# CNC-MainBoard.net
KiCad netlist of a schematic drawn in EAGLE
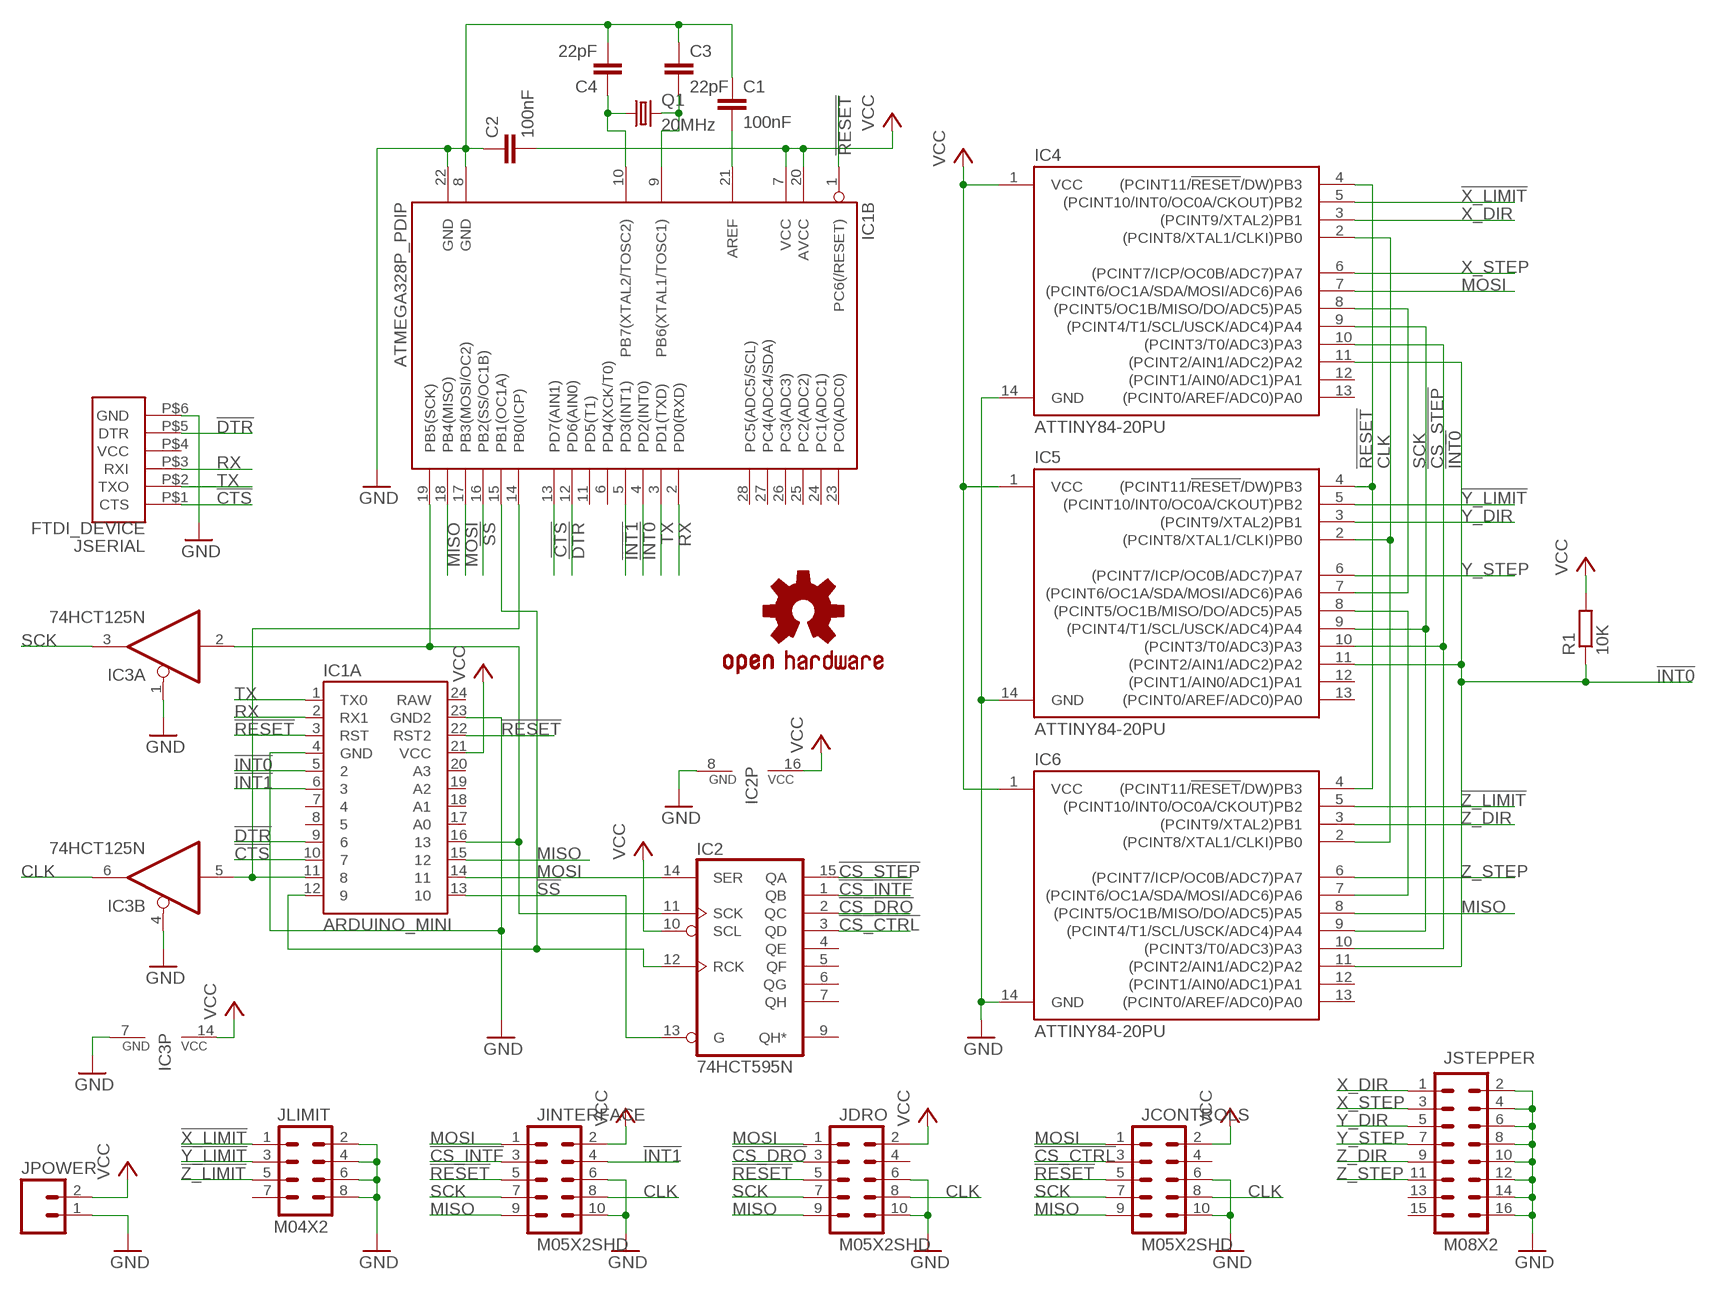
[diagram p0: schematic, sheet 1]

(export (version "E")
  (design (tool "Eeschema 10.0.6"))
  (components
    (comp (ref "C1")
      (value "100nF")
      (footprint "eagle-import:C050-025X075")
      (libsource (lib "eagle-import") (part "C-EU050-025X075"))
    )
    (comp (ref "C2")
      (value "100nF")
      (footprint "eagle-import:C050-025X075")
      (libsource (lib "eagle-import") (part "C-EU050-025X075"))
    )
    (comp (ref "C3")
      (value "22pF")
      (footprint "eagle-import:C050-025X075")
      (libsource (lib "eagle-import") (part "C-EU050-025X075"))
    )
    (comp (ref "C4")
      (value "22pF")
      (footprint "eagle-import:C050-025X075")
      (libsource (lib "eagle-import") (part "C-EU050-025X075"))
    )
    (comp (ref "IC1A")
      (value "ARDUINO_MINI")
      (footprint "eagle-import:ARDUINO_MINI")
      (libsource (lib "eagle-import") (part "ARDUINO_MINI"))
    )
    (comp (ref "IC1B")
      (value "ATMEGA328P_PDIP")
      (footprint "eagle-import:DIL28-3")
      (libsource (lib "eagle-import") (part "ATMEGA328P_PDIP"))
    )
    (comp (ref "IC2")
      (value "74HCT595N")
      (footprint "eagle-import:DIL16")
      (libsource (lib "eagle-import") (part "74595NHCT"))
    )
    (comp (ref "IC3")
      (value "74HCT125N")
      (footprint "eagle-import:DIL14")
      (libsource (lib "eagle-import") (part "74125NHCT"))
    )
    (comp (ref "IC4")
      (value "ATTINY84-20PU")
      (footprint "eagle-import:DIL14")
      (libsource (lib "eagle-import") (part "ATTINY84PU-20"))
    )
    (comp (ref "IC5")
      (value "ATTINY84-20PU")
      (footprint "eagle-import:DIL14")
      (libsource (lib "eagle-import") (part "ATTINY84PU-20"))
    )
    (comp (ref "IC6")
      (value "ATTINY84-20PU")
      (footprint "eagle-import:DIL14")
      (libsource (lib "eagle-import") (part "ATTINY84PU-20"))
    )
    (comp (ref "JCONTROLS")
      (value "M05X2SHD")
      (footprint "eagle-import:2X5-SHROUDED")
      (libsource (lib "eagle-import") (part "M05X2SHD"))
    )
    (comp (ref "JDRO")
      (value "M05X2SHD")
      (footprint "eagle-import:2X5-SHROUDED")
      (libsource (lib "eagle-import") (part "M05X2SHD"))
    )
    (comp (ref "JINTERFACE")
      (value "M05X2SHD")
      (footprint "eagle-import:2X5-SHROUDED")
      (libsource (lib "eagle-import") (part "M05X2SHD"))
    )
    (comp (ref "JLIMIT")
      (value "M04X2")
      (footprint "eagle-import:2X4")
      (libsource (lib "eagle-import") (part "M04X2"))
    )
    (comp (ref "JPOWER")
      (value "M02POLAR")
      (footprint "eagle-import:MOLEX-1X2")
      (libsource (lib "eagle-import") (part "M02POLAR"))
    )
    (comp (ref "JSERIAL")
      (value "FTDI_DEVICE")
      (footprint "eagle-import:FTDI_DEVICE_SIDE")
      (libsource (lib "eagle-import") (part "FTDI_DEVICE"))
    )
    (comp (ref "JSTEPPER")
      (value "M08X2")
      (footprint "eagle-import:2X8")
      (libsource (lib "eagle-import") (part "M08X2"))
    )
    (comp (ref "Q1")
      (value "20MHz")
      (footprint "eagle-import:HC49U-V")
      (libsource (lib "eagle-import") (part "CRYSTALHC49U-V"))
    )
    (comp (ref "R1")
      (value "10K")
      (footprint "eagle-import:0207_10")
      (libsource (lib "eagle-import") (part "R-EU_0207/10"))
    )
    (comp (ref "U$1")
      (value "SPARKFUN_OSHW-LOGOL")
      (footprint "eagle-import:SPARKFUN_OSHW-LOGO-L")
      (libsource (lib "eagle-import") (part "SPARKFUN_OSHW-LOGOL"))
    )
  )
  (nets
    (net (code "1") (name "/CLK") (class "Default")
      (node (ref "IC3") (pin "6") (pinfunction "O_6") (pintype "tri_state"))
      (node (ref "IC4") (pin "2") (pinfunction "(PCINT8/XTAL1/CLKI)PB0_2") (pintype "bidirectional"))
      (node (ref "IC5") (pin "2") (pinfunction "(PCINT8/XTAL1/CLKI)PB0_2") (pintype "bidirectional"))
      (node (ref "IC6") (pin "2") (pinfunction "(PCINT8/XTAL1/CLKI)PB0_2") (pintype "bidirectional"))
      (node (ref "JCONTROLS") (pin "8") (pinfunction "8_8") (pintype "passive"))
      (node (ref "JDRO") (pin "8") (pinfunction "8_8") (pintype "passive"))
      (node (ref "JINTERFACE") (pin "8") (pinfunction "8_8") (pintype "passive"))
    )
    (net (code "2") (name "/MISO") (class "Default")
      (node (ref "IC1A") (pin "15") (pinfunction "12_15") (pintype "bidirectional"))
      (node (ref "IC1B") (pin "18") (pinfunction "PB4(MISO)_18") (pintype "bidirectional"))
      (node (ref "IC6") (pin "8") (pinfunction "(PCINT5/OC1B/MISO/DO/ADC5)PA5_8") (pintype "bidirectional"))
      (node (ref "JCONTROLS") (pin "9") (pinfunction "9_9") (pintype "passive"))
      (node (ref "JDRO") (pin "9") (pinfunction "9_9") (pintype "passive"))
      (node (ref "JINTERFACE") (pin "9") (pinfunction "9_9") (pintype "passive"))
    )
    (net (code "3") (name "/MOSI") (class "Default")
      (node (ref "IC1A") (pin "14") (pinfunction "11_14") (pintype "bidirectional"))
      (node (ref "IC1B") (pin "17") (pinfunction "PB3(MOSI/OC2)_17") (pintype "bidirectional"))
      (node (ref "IC2") (pin "14") (pinfunction "SER_14") (pintype "input"))
      (node (ref "IC4") (pin "7") (pinfunction "(PCINT6/OC1A/SDA/MOSI/ADC6)PA6_7") (pintype "bidirectional"))
      (node (ref "JCONTROLS") (pin "1") (pinfunction "1_1") (pintype "passive"))
      (node (ref "JDRO") (pin "1") (pinfunction "1_1") (pintype "passive"))
      (node (ref "JINTERFACE") (pin "1") (pinfunction "1_1") (pintype "passive"))
    )
    (net (code "4") (name "/RX") (class "Default")
      (node (ref "IC1A") (pin "2") (pinfunction "RX1_2") (pintype "bidirectional"))
      (node (ref "IC1B") (pin "2") (pinfunction "PD0(RXD)_2") (pintype "bidirectional"))
      (node (ref "JSERIAL") (pin "P$3") (pinfunction "RXI_P$3") (pintype "bidirectional"))
    )
    (net (code "5") (name "/SCK") (class "Default")
      (node (ref "IC3") (pin "3") (pinfunction "O_3") (pintype "tri_state"))
      (node (ref "IC4") (pin "9") (pinfunction "(PCINT4/T1/SCL/USCK/ADC4)PA4_9") (pintype "bidirectional"))
      (node (ref "IC5") (pin "9") (pinfunction "(PCINT4/T1/SCL/USCK/ADC4)PA4_9") (pintype "bidirectional"))
      (node (ref "IC6") (pin "9") (pinfunction "(PCINT4/T1/SCL/USCK/ADC4)PA4_9") (pintype "bidirectional"))
      (node (ref "JCONTROLS") (pin "7") (pinfunction "7_7") (pintype "passive"))
      (node (ref "JDRO") (pin "7") (pinfunction "7_7") (pintype "passive"))
      (node (ref "JINTERFACE") (pin "7") (pinfunction "7_7") (pintype "passive"))
    )
    (net (code "6") (name "/TX") (class "Default")
      (node (ref "IC1A") (pin "1") (pinfunction "TX0_1") (pintype "bidirectional"))
      (node (ref "IC1B") (pin "3") (pinfunction "PD1(TXD)_3") (pintype "bidirectional"))
      (node (ref "JSERIAL") (pin "P$2") (pinfunction "TXO_P$2") (pintype "bidirectional"))
    )
    (net (code "7") (name "/X_DIR") (class "Default")
      (node (ref "IC4") (pin "3") (pinfunction "(PCINT9/XTAL2)PB1_3") (pintype "bidirectional"))
      (node (ref "JSTEPPER") (pin "1") (pinfunction "1_1") (pintype "passive"))
    )
    (net (code "8") (name "/X_STEP") (class "Default")
      (node (ref "IC4") (pin "6") (pinfunction "(PCINT7/ICP/OC0B/ADC7)PA7_6") (pintype "bidirectional"))
      (node (ref "JSTEPPER") (pin "3") (pinfunction "3_3") (pintype "passive"))
    )
    (net (code "9") (name "/Y_DIR") (class "Default")
      (node (ref "IC5") (pin "3") (pinfunction "(PCINT9/XTAL2)PB1_3") (pintype "bidirectional"))
      (node (ref "JSTEPPER") (pin "5") (pinfunction "5_5") (pintype "passive"))
    )
    (net (code "10") (name "/Y_STEP") (class "Default")
      (node (ref "IC5") (pin "6") (pinfunction "(PCINT7/ICP/OC0B/ADC7)PA7_6") (pintype "bidirectional"))
      (node (ref "JSTEPPER") (pin "7") (pinfunction "7_7") (pintype "passive"))
    )
    (net (code "11") (name "/Z_DIR") (class "Default")
      (node (ref "IC6") (pin "3") (pinfunction "(PCINT9/XTAL2)PB1_3") (pintype "bidirectional"))
      (node (ref "JSTEPPER") (pin "9") (pinfunction "9_9") (pintype "passive"))
    )
    (net (code "12") (name "/Z_STEP") (class "Default")
      (node (ref "IC6") (pin "6") (pinfunction "(PCINT7/ICP/OC0B/ADC7)PA7_6") (pintype "bidirectional"))
      (node (ref "JSTEPPER") (pin "11") (pinfunction "11_11") (pintype "passive"))
    )
    (net (code "13") (name "/~{CS_CTRL}") (class "Default")
      (node (ref "IC2") (pin "3") (pinfunction "QD_3") (pintype "tri_state"))
      (node (ref "JCONTROLS") (pin "3") (pinfunction "3_3") (pintype "passive"))
    )
    (net (code "14") (name "/~{CS_DRO}") (class "Default")
      (node (ref "IC2") (pin "2") (pinfunction "QC_2") (pintype "tri_state"))
      (node (ref "JDRO") (pin "3") (pinfunction "3_3") (pintype "passive"))
    )
    (net (code "15") (name "/~{CS_INTF}") (class "Default")
      (node (ref "IC2") (pin "1") (pinfunction "QB_1") (pintype "tri_state"))
      (node (ref "JINTERFACE") (pin "3") (pinfunction "3_3") (pintype "passive"))
    )
    (net (code "16") (name "/~{CS_STEP}") (class "Default")
      (node (ref "IC2") (pin "15") (pinfunction "QA_15") (pintype "tri_state"))
      (node (ref "IC4") (pin "10") (pinfunction "(PCINT3/T0/ADC3)PA3_10") (pintype "bidirectional"))
      (node (ref "IC5") (pin "10") (pinfunction "(PCINT3/T0/ADC3)PA3_10") (pintype "bidirectional"))
      (node (ref "IC6") (pin "10") (pinfunction "(PCINT3/T0/ADC3)PA3_10") (pintype "bidirectional"))
    )
    (net (code "17") (name "/~{CTS}") (class "Default")
      (node (ref "IC1A") (pin "10") (pinfunction "7_10") (pintype "bidirectional"))
      (node (ref "IC1B") (pin "13") (pinfunction "PD7(AIN1)_13") (pintype "bidirectional"))
      (node (ref "JSERIAL") (pin "P$1") (pinfunction "CTS_P$1") (pintype "bidirectional"))
    )
    (net (code "18") (name "/~{DTR}") (class "Default")
      (node (ref "IC1A") (pin "9") (pinfunction "6_9") (pintype "bidirectional"))
      (node (ref "IC1B") (pin "12") (pinfunction "PD6(AIN0)_12") (pintype "bidirectional"))
      (node (ref "JSERIAL") (pin "P$5") (pinfunction "DTR_P$5") (pintype "bidirectional"))
    )
    (net (code "19") (name "/~{INT0}") (class "Default")
      (node (ref "IC1A") (pin "5") (pinfunction "2_5") (pintype "bidirectional"))
      (node (ref "IC1B") (pin "4") (pinfunction "PD2(INT0)_4") (pintype "bidirectional"))
      (node (ref "IC4") (pin "11") (pinfunction "(PCINT2/AIN1/ADC2)PA2_11") (pintype "bidirectional"))
      (node (ref "IC5") (pin "11") (pinfunction "(PCINT2/AIN1/ADC2)PA2_11") (pintype "bidirectional"))
      (node (ref "IC6") (pin "11") (pinfunction "(PCINT2/AIN1/ADC2)PA2_11") (pintype "bidirectional"))
      (node (ref "R1") (pin "1") (pinfunction "1_1") (pintype "passive"))
    )
    (net (code "20") (name "/~{INT1}") (class "Default")
      (node (ref "IC1A") (pin "6") (pinfunction "3_6") (pintype "bidirectional"))
      (node (ref "IC1B") (pin "5") (pinfunction "PD3(INT1)_5") (pintype "bidirectional"))
      (node (ref "JINTERFACE") (pin "4") (pinfunction "4_4") (pintype "passive"))
    )
    (net (code "21") (name "/~{RESET}") (class "Default")
      (node (ref "IC1A") (pin "22") (pinfunction "RST2_22") (pintype "bidirectional"))
      (node (ref "IC1A") (pin "3") (pinfunction "RST_3") (pintype "bidirectional"))
      (node (ref "IC1B") (pin "1") (pinfunction "PC6(/RESET)_1") (pintype "bidirectional"))
      (node (ref "IC4") (pin "4") (pinfunction "(PCINT11/~{RESET}/DW)PB3_4") (pintype "bidirectional"))
      (node (ref "IC5") (pin "4") (pinfunction "(PCINT11/~{RESET}/DW)PB3_4") (pintype "bidirectional"))
      (node (ref "IC6") (pin "4") (pinfunction "(PCINT11/~{RESET}/DW)PB3_4") (pintype "bidirectional"))
      (node (ref "JCONTROLS") (pin "5") (pinfunction "5_5") (pintype "passive"))
      (node (ref "JDRO") (pin "5") (pinfunction "5_5") (pintype "passive"))
      (node (ref "JINTERFACE") (pin "5") (pinfunction "5_5") (pintype "passive"))
    )
    (net (code "22") (name "/~{SS}") (class "Default")
      (node (ref "IC1A") (pin "13") (pinfunction "10_13") (pintype "bidirectional"))
      (node (ref "IC1B") (pin "16") (pinfunction "PB2(SS/OC1B)_16") (pintype "bidirectional"))
      (node (ref "IC2") (pin "13") (pinfunction "G_13") (pintype "input"))
    )
    (net (code "23") (name "/~{X_LIMIT}") (class "Default")
      (node (ref "IC4") (pin "5") (pinfunction "(PCINT10/INT0/OC0A/CKOUT)PB2_5") (pintype "bidirectional"))
      (node (ref "JLIMIT") (pin "1") (pinfunction "1_1") (pintype "passive"))
    )
    (net (code "24") (name "/~{Y_LIMIT}") (class "Default")
      (node (ref "IC5") (pin "5") (pinfunction "(PCINT10/INT0/OC0A/CKOUT)PB2_5") (pintype "bidirectional"))
      (node (ref "JLIMIT") (pin "3") (pinfunction "3_3") (pintype "passive"))
    )
    (net (code "25") (name "/~{Z_LIMIT}") (class "Default")
      (node (ref "IC6") (pin "5") (pinfunction "(PCINT10/INT0/OC0A/CKOUT)PB2_5") (pintype "bidirectional"))
      (node (ref "JLIMIT") (pin "5") (pinfunction "5_5") (pintype "passive"))
    )
    (net (code "26") (name "GND") (class "Default")
      (node (ref "C1") (pin "1") (pinfunction "1_1") (pintype "passive"))
      (node (ref "C2") (pin "1") (pinfunction "1_1") (pintype "passive"))
      (node (ref "C3") (pin "1") (pinfunction "1_1") (pintype "passive"))
      (node (ref "C4") (pin "2") (pinfunction "2_2") (pintype "passive"))
      (node (ref "IC1A") (pin "23") (pinfunction "GND2_23") (pintype "bidirectional"))
      (node (ref "IC1A") (pin "4") (pinfunction "GND_4") (pintype "bidirectional"))
      (node (ref "IC1B") (pin "22") (pinfunction "GND_22") (pintype "bidirectional"))
      (node (ref "IC1B") (pin "8") (pinfunction "GND_8") (pintype "bidirectional"))
      (node (ref "IC2") (pin "8") (pinfunction "GND_8") (pintype "power_in"))
      (node (ref "IC3") (pin "1") (pinfunction "OE_1") (pintype "input"))
      (node (ref "IC3") (pin "4") (pinfunction "OE_4") (pintype "input"))
      (node (ref "IC3") (pin "7") (pinfunction "GND_7") (pintype "power_in"))
      (node (ref "IC4") (pin "14") (pinfunction "GND_14") (pintype "bidirectional"))
      (node (ref "IC5") (pin "14") (pinfunction "GND_14") (pintype "bidirectional"))
      (node (ref "IC6") (pin "14") (pinfunction "GND_14") (pintype "bidirectional"))
      (node (ref "JCONTROLS") (pin "10") (pinfunction "10_10") (pintype "passive"))
      (node (ref "JCONTROLS") (pin "6") (pinfunction "6_6") (pintype "passive"))
      (node (ref "JDRO") (pin "10") (pinfunction "10_10") (pintype "passive"))
      (node (ref "JDRO") (pin "6") (pinfunction "6_6") (pintype "passive"))
      (node (ref "JINTERFACE") (pin "10") (pinfunction "10_10") (pintype "passive"))
      (node (ref "JINTERFACE") (pin "6") (pinfunction "6_6") (pintype "passive"))
      (node (ref "JLIMIT") (pin "2") (pinfunction "2_2") (pintype "passive"))
      (node (ref "JLIMIT") (pin "4") (pinfunction "4_4") (pintype "passive"))
      (node (ref "JLIMIT") (pin "6") (pinfunction "6_6") (pintype "passive"))
      (node (ref "JLIMIT") (pin "8") (pinfunction "8_8") (pintype "passive"))
      (node (ref "JPOWER") (pin "1") (pinfunction "1_1") (pintype "passive"))
      (node (ref "JSERIAL") (pin "P$6") (pinfunction "GND_P$6") (pintype "bidirectional"))
      (node (ref "JSTEPPER") (pin "10") (pinfunction "10_10") (pintype "passive"))
      (node (ref "JSTEPPER") (pin "12") (pinfunction "12_12") (pintype "passive"))
      (node (ref "JSTEPPER") (pin "14") (pinfunction "14_14") (pintype "passive"))
      (node (ref "JSTEPPER") (pin "16") (pinfunction "16_16") (pintype "passive"))
      (node (ref "JSTEPPER") (pin "2") (pinfunction "2_2") (pintype "passive"))
      (node (ref "JSTEPPER") (pin "4") (pinfunction "4_4") (pintype "passive"))
      (node (ref "JSTEPPER") (pin "6") (pinfunction "6_6") (pintype "passive"))
      (node (ref "JSTEPPER") (pin "8") (pinfunction "8_8") (pintype "passive"))
    )
    (net (code "27") (name "Net-(IC1A-8)") (class "Default")
      (node (ref "IC1A") (pin "11") (pinfunction "8_11") (pintype "bidirectional"))
      (node (ref "IC1B") (pin "14") (pinfunction "PB0(ICP)_14") (pintype "bidirectional"))
      (node (ref "IC3") (pin "5") (pinfunction "I_5") (pintype "input"))
    )
    (net (code "28") (name "Net-(IC1A-9)") (class "Default")
      (node (ref "IC1A") (pin "12") (pinfunction "9_12") (pintype "bidirectional"))
      (node (ref "IC1B") (pin "15") (pinfunction "PB1(OC1A)_15") (pintype "bidirectional"))
      (node (ref "IC2") (pin "12") (pinfunction "RCK_12") (pintype "input"))
    )
    (net (code "29") (name "Net-(IC1A-13)") (class "Default")
      (node (ref "IC1A") (pin "16") (pinfunction "13_16") (pintype "bidirectional"))
      (node (ref "IC1B") (pin "19") (pinfunction "PB5(SCK)_19") (pintype "bidirectional"))
      (node (ref "IC2") (pin "11") (pinfunction "SCK_11") (pintype "input"))
      (node (ref "IC3") (pin "2") (pinfunction "I_2") (pintype "input"))
    )
    (net (code "30") (name "Net-(IC1B-AREF)") (class "Default")
      (node (ref "C1") (pin "2") (pinfunction "2_2") (pintype "passive"))
      (node (ref "IC1B") (pin "21") (pinfunction "AREF_21") (pintype "bidirectional"))
    )
    (net (code "31") (name "Net-(IC1B-PB6(XTAL1{slash}TOSC1))") (class "Default")
      (node (ref "C3") (pin "2") (pinfunction "2_2") (pintype "passive"))
      (node (ref "IC1B") (pin "9") (pinfunction "PB6(XTAL1/TOSC1)_9") (pintype "bidirectional"))
      (node (ref "Q1") (pin "2") (pinfunction "2_2") (pintype "passive"))
    )
    (net (code "32") (name "Net-(IC1B-PB7(XTAL2{slash}TOSC2))") (class "Default")
      (node (ref "C4") (pin "1") (pinfunction "1_1") (pintype "passive"))
      (node (ref "IC1B") (pin "10") (pinfunction "PB7(XTAL2/TOSC2)_10") (pintype "bidirectional"))
      (node (ref "Q1") (pin "1") (pinfunction "1_1") (pintype "passive"))
    )
    (net (code "33") (name "Net-(IC4-(PCINT5{slash}OC1B{slash}MISO{slash}DO{slash}ADC5)PA5)") (class "Default")
      (node (ref "IC4") (pin "8") (pinfunction "(PCINT5/OC1B/MISO/DO/ADC5)PA5_8") (pintype "bidirectional"))
      (node (ref "IC5") (pin "7") (pinfunction "(PCINT6/OC1A/SDA/MOSI/ADC6)PA6_7") (pintype "bidirectional"))
    )
    (net (code "34") (name "Net-(IC5-(PCINT5{slash}OC1B{slash}MISO{slash}DO{slash}ADC5)PA5)") (class "Default")
      (node (ref "IC5") (pin "8") (pinfunction "(PCINT5/OC1B/MISO/DO/ADC5)PA5_8") (pintype "bidirectional"))
      (node (ref "IC6") (pin "7") (pinfunction "(PCINT6/OC1A/SDA/MOSI/ADC6)PA6_7") (pintype "bidirectional"))
    )
    (net (code "35") (name "VCC") (class "Default")
      (node (ref "C2") (pin "2") (pinfunction "2_2") (pintype "passive"))
      (node (ref "IC1A") (pin "21") (pinfunction "VCC_21") (pintype "bidirectional"))
      (node (ref "IC1B") (pin "20") (pinfunction "AVCC_20") (pintype "bidirectional"))
      (node (ref "IC1B") (pin "7") (pinfunction "VCC_7") (pintype "bidirectional"))
      (node (ref "IC2") (pin "10") (pinfunction "SCL_10") (pintype "input"))
      (node (ref "IC2") (pin "16") (pinfunction "VCC_16") (pintype "power_in"))
      (node (ref "IC3") (pin "14") (pinfunction "VCC_14") (pintype "power_in"))
      (node (ref "IC4") (pin "1") (pinfunction "VCC_1") (pintype "bidirectional"))
      (node (ref "IC5") (pin "1") (pinfunction "VCC_1") (pintype "bidirectional"))
      (node (ref "IC6") (pin "1") (pinfunction "VCC_1") (pintype "bidirectional"))
      (node (ref "JCONTROLS") (pin "2") (pinfunction "2_2") (pintype "passive"))
      (node (ref "JDRO") (pin "2") (pinfunction "2_2") (pintype "passive"))
      (node (ref "JINTERFACE") (pin "2") (pinfunction "2_2") (pintype "passive"))
      (node (ref "JPOWER") (pin "2") (pinfunction "2_2") (pintype "passive"))
      (node (ref "R1") (pin "2") (pinfunction "2_2") (pintype "passive"))
    )
    (net (code "36") (name "unconnected-(IC1A-4-Pad7)") (class "Default")
      (node (ref "IC1A") (pin "7") (pinfunction "4_7") (pintype "bidirectional"))
    )
    (net (code "37") (name "unconnected-(IC1A-5-Pad8)") (class "Default")
      (node (ref "IC1A") (pin "8") (pinfunction "5_8") (pintype "bidirectional"))
    )
    (net (code "38") (name "unconnected-(IC1A-A0-Pad17)") (class "Default")
      (node (ref "IC1A") (pin "17") (pinfunction "A0_17") (pintype "bidirectional"))
    )
    (net (code "39") (name "unconnected-(IC1A-A1-Pad18)") (class "Default")
      (node (ref "IC1A") (pin "18") (pinfunction "A1_18") (pintype "bidirectional"))
    )
    (net (code "40") (name "unconnected-(IC1A-A2-Pad19)") (class "Default")
      (node (ref "IC1A") (pin "19") (pinfunction "A2_19") (pintype "bidirectional"))
    )
    (net (code "41") (name "unconnected-(IC1A-A3-Pad20)") (class "Default")
      (node (ref "IC1A") (pin "20") (pinfunction "A3_20") (pintype "bidirectional"))
    )
    (net (code "42") (name "unconnected-(IC1A-RAW-Pad24)") (class "Default")
      (node (ref "IC1A") (pin "24") (pinfunction "RAW_24") (pintype "bidirectional"))
    )
    (net (code "43") (name "unconnected-(IC1B-PC0(ADC0)-Pad23)") (class "Default")
      (node (ref "IC1B") (pin "23") (pinfunction "PC0(ADC0)_23") (pintype "bidirectional"))
    )
    (net (code "44") (name "unconnected-(IC1B-PC1(ADC1)-Pad24)") (class "Default")
      (node (ref "IC1B") (pin "24") (pinfunction "PC1(ADC1)_24") (pintype "bidirectional"))
    )
    (net (code "45") (name "unconnected-(IC1B-PC2(ADC2)-Pad25)") (class "Default")
      (node (ref "IC1B") (pin "25") (pinfunction "PC2(ADC2)_25") (pintype "bidirectional"))
    )
    (net (code "46") (name "unconnected-(IC1B-PC3(ADC3)-Pad26)") (class "Default")
      (node (ref "IC1B") (pin "26") (pinfunction "PC3(ADC3)_26") (pintype "bidirectional"))
    )
    (net (code "47") (name "unconnected-(IC1B-PC4(ADC4{slash}SDA)-Pad27)") (class "Default")
      (node (ref "IC1B") (pin "27") (pinfunction "PC4(ADC4/SDA)_27") (pintype "bidirectional"))
    )
    (net (code "48") (name "unconnected-(IC1B-PC5(ADC5{slash}SCL)-Pad28)") (class "Default")
      (node (ref "IC1B") (pin "28") (pinfunction "PC5(ADC5/SCL)_28") (pintype "bidirectional"))
    )
    (net (code "49") (name "unconnected-(IC1B-PD4(XCK{slash}T0)-Pad6)") (class "Default")
      (node (ref "IC1B") (pin "6") (pinfunction "PD4(XCK/T0)_6") (pintype "bidirectional"))
    )
    (net (code "50") (name "unconnected-(IC1B-PD5(T1)-Pad11)") (class "Default")
      (node (ref "IC1B") (pin "11") (pinfunction "PD5(T1)_11") (pintype "bidirectional"))
    )
    (net (code "51") (name "unconnected-(IC2A-QE-Pad4)") (class "Default")
      (node (ref "IC2") (pin "4") (pinfunction "QE_4") (pintype "tri_state"))
    )
    (net (code "52") (name "unconnected-(IC2A-QF-Pad5)") (class "Default")
      (node (ref "IC2") (pin "5") (pinfunction "QF_5") (pintype "tri_state"))
    )
    (net (code "53") (name "unconnected-(IC2A-QG-Pad6)") (class "Default")
      (node (ref "IC2") (pin "6") (pinfunction "QG_6") (pintype "tri_state"))
    )
    (net (code "54") (name "unconnected-(IC2A-QH*-Pad9)") (class "Default")
      (node (ref "IC2") (pin "9") (pinfunction "QH*_9") (pintype "tri_state"))
    )
    (net (code "55") (name "unconnected-(IC2A-QH-Pad7)") (class "Default")
      (node (ref "IC2") (pin "7") (pinfunction "QH_7") (pintype "tri_state"))
    )
    (net (code "56") (name "unconnected-(IC4-(PCINT0{slash}AREF{slash}ADC0)PA0-Pad13)") (class "Default")
      (node (ref "IC4") (pin "13") (pinfunction "(PCINT0/AREF/ADC0)PA0_13") (pintype "bidirectional"))
    )
    (net (code "57") (name "unconnected-(IC4-(PCINT1{slash}AIN0{slash}ADC1)PA1-Pad12)") (class "Default")
      (node (ref "IC4") (pin "12") (pinfunction "(PCINT1/AIN0/ADC1)PA1_12") (pintype "bidirectional"))
    )
    (net (code "58") (name "unconnected-(IC5-(PCINT0{slash}AREF{slash}ADC0)PA0-Pad13)") (class "Default")
      (node (ref "IC5") (pin "13") (pinfunction "(PCINT0/AREF/ADC0)PA0_13") (pintype "bidirectional"))
    )
    (net (code "59") (name "unconnected-(IC5-(PCINT1{slash}AIN0{slash}ADC1)PA1-Pad12)") (class "Default")
      (node (ref "IC5") (pin "12") (pinfunction "(PCINT1/AIN0/ADC1)PA1_12") (pintype "bidirectional"))
    )
    (net (code "60") (name "unconnected-(IC6-(PCINT0{slash}AREF{slash}ADC0)PA0-Pad13)") (class "Default")
      (node (ref "IC6") (pin "13") (pinfunction "(PCINT0/AREF/ADC0)PA0_13") (pintype "bidirectional"))
    )
    (net (code "61") (name "unconnected-(IC6-(PCINT1{slash}AIN0{slash}ADC1)PA1-Pad12)") (class "Default")
      (node (ref "IC6") (pin "12") (pinfunction "(PCINT1/AIN0/ADC1)PA1_12") (pintype "bidirectional"))
    )
    (net (code "62") (name "unconnected-(JCONTROLS-Pad4)") (class "Default")
      (node (ref "JCONTROLS") (pin "4") (pinfunction "4_4") (pintype "passive"))
    )
    (net (code "63") (name "unconnected-(JDRO-Pad4)") (class "Default")
      (node (ref "JDRO") (pin "4") (pinfunction "4_4") (pintype "passive"))
    )
    (net (code "64") (name "unconnected-(JLIMIT-Pad7)") (class "Default")
      (node (ref "JLIMIT") (pin "7") (pinfunction "7_7") (pintype "passive"))
    )
    (net (code "65") (name "unconnected-(JSERIAL-VCC-PadP$4)") (class "Default")
      (node (ref "JSERIAL") (pin "P$4") (pinfunction "VCC_P$4") (pintype "bidirectional"))
    )
    (net (code "66") (name "unconnected-(JSTEPPER-Pad13)") (class "Default")
      (node (ref "JSTEPPER") (pin "13") (pinfunction "13_13") (pintype "passive"))
    )
    (net (code "67") (name "unconnected-(JSTEPPER-Pad15)") (class "Default")
      (node (ref "JSTEPPER") (pin "15") (pinfunction "15_15") (pintype "passive"))
    )
  )
)
